# BLUESatPC104Template.net
KiCad netlist of a schematic drawn in Altium Designer
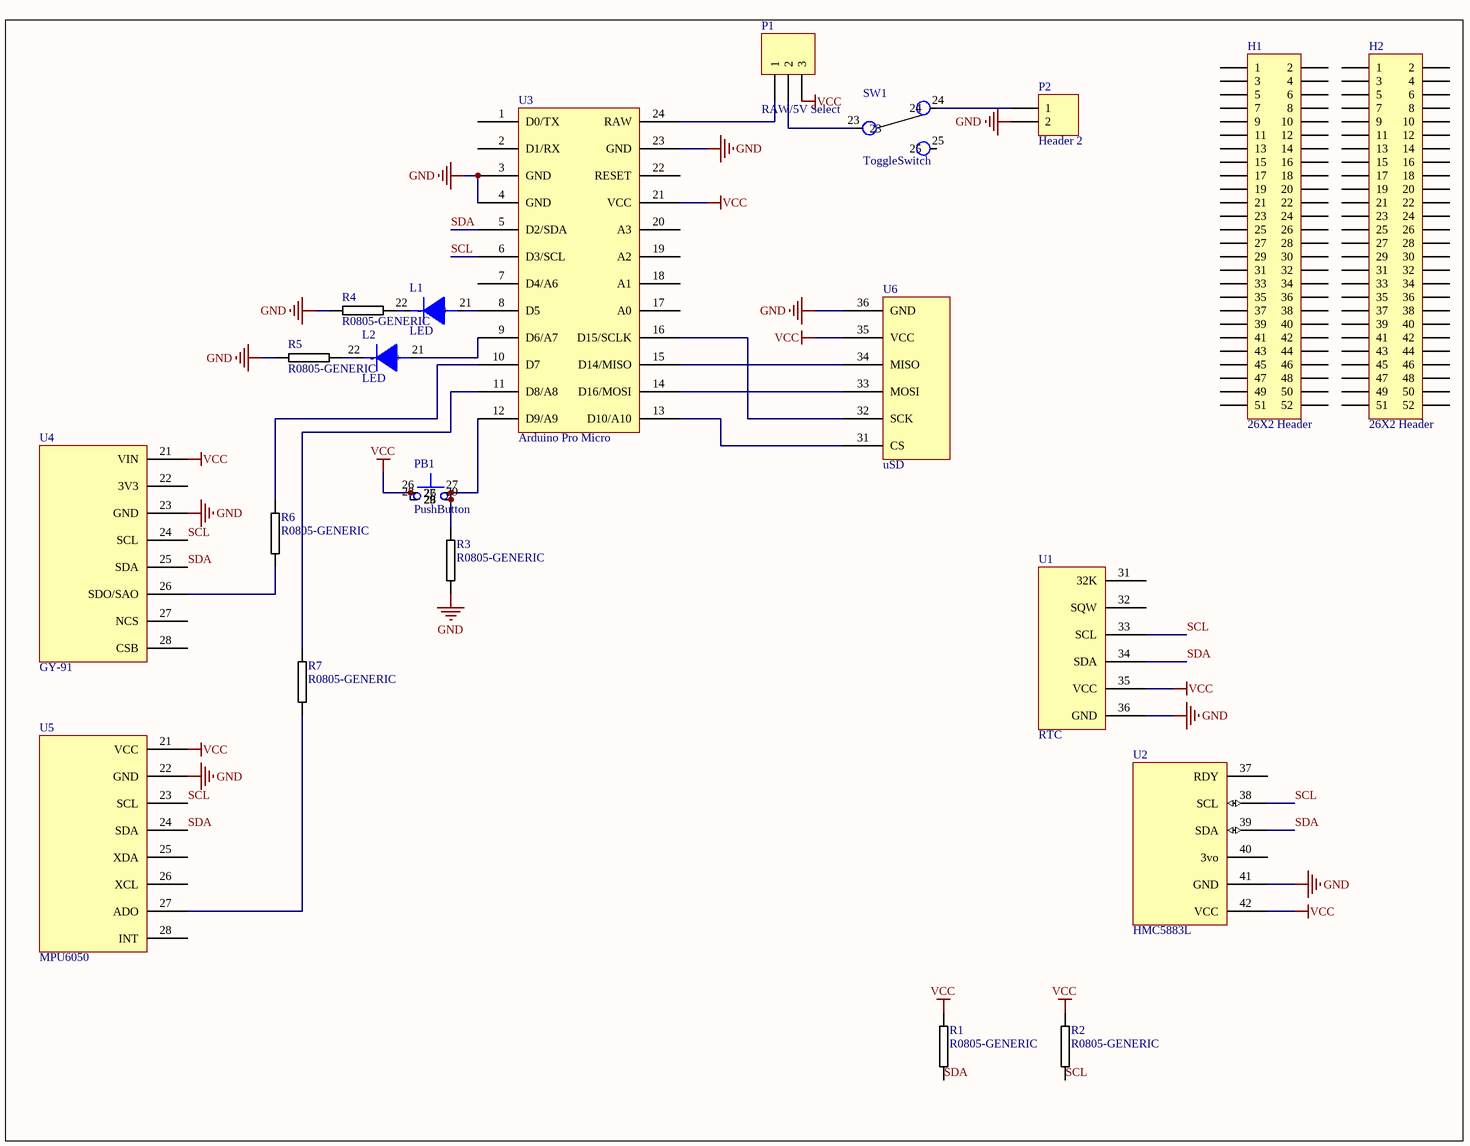
[diagram p0: BLUESatPC104Template.SchDoc]

(export (version "E")
  (design (tool "Eeschema 10.0.6"))
  (components
    (comp (ref "H1")
      (value "26X2 Header")
      (footprint "26X2 Header")
      (libsource (lib "CustomParts") (part "26X2 Header"))
    )
    (comp (ref "H2")
      (value "26X2 Header")
      (footprint "26X2 Header")
      (libsource (lib "CustomParts") (part "26X2 Header"))
    )
    (comp (ref "L1") (value "LED") (footprint "LEDFOOTPRINT") (libsource (lib "Schlib1") (part "LED")))
    (comp (ref "L2") (value "LED") (footprint "LEDFOOTPRINT") (libsource (lib "Schlib1") (part "LED")))
    (comp (ref "P1")
      (value "RAW/5V Select")
      (footprint "HDR1X3")
      (description "Header, 3-Pin")
      (fields (field (name "PUBLISHER") "Altium Limited"))
      (libsource (lib "Miscellaneous Connectors") (part "Header 3"))
    )
    (comp (ref "P2")
      (value "Header 2")
      (footprint "HDR1X2")
      (description "Header, 2-Pin")
      (fields (field (name "PUBLISHER") "Altium Limited"))
      (libsource (lib "Miscellaneous Connectors") (part "Header 2"))
    )
    (comp (ref "PB1")
      (value "PushButton")
      (footprint "PCBComponent_1")
      (libsource (lib "Schlib1") (part "PushButton"))
    )
    (comp (ref "R1")
      (value "R0805-GENERIC")
      (footprint "0805R-GENERIC")
      (description "GENERIC RESISTOR 0805")
      (libsource (lib "vh_altium_library") (part "R0805-GENERIC"))
    )
    (comp (ref "R2")
      (value "R0805-GENERIC")
      (footprint "0805R-GENERIC")
      (description "GENERIC RESISTOR 0805")
      (libsource (lib "vh_altium_library") (part "R0805-GENERIC"))
    )
    (comp (ref "R3")
      (value "R0805-GENERIC")
      (footprint "0805R-GENERIC")
      (description "GENERIC RESISTOR 0805")
      (libsource (lib "vh_altium_library") (part "R0805-GENERIC"))
    )
    (comp (ref "R4")
      (value "R0805-GENERIC")
      (footprint "0805R-GENERIC")
      (description "GENERIC RESISTOR 0805")
      (libsource (lib "vh_altium_library") (part "R0805-GENERIC"))
    )
    (comp (ref "R5")
      (value "R0805-GENERIC")
      (footprint "0805R-GENERIC")
      (description "GENERIC RESISTOR 0805")
      (libsource (lib "vh_altium_library") (part "R0805-GENERIC"))
    )
    (comp (ref "R6")
      (value "R0805-GENERIC")
      (footprint "0805R-GENERIC")
      (description "GENERIC RESISTOR 0805")
      (libsource (lib "vh_altium_library") (part "R0805-GENERIC"))
    )
    (comp (ref "R7")
      (value "R0805-GENERIC")
      (footprint "0805R-GENERIC")
      (description "GENERIC RESISTOR 0805")
      (libsource (lib "vh_altium_library") (part "R0805-GENERIC"))
    )
    (comp (ref "SW1")
      (value "ToggleSwitch")
      (footprint "SWITCHFOOTPRINT")
      (libsource (lib "Schlib1") (part "ToggleSwitch"))
    )
    (comp (ref "U1") (value "RTC") (footprint "DS3FOOTPRINT") (libsource (lib "Schlib1") (part "RTC")))
    (comp (ref "U2")
      (value "HMC5883L")
      (footprint "HMCFootprint")
      (libsource (lib "Schlib1") (part "HMC5883L"))
    )
    (comp (ref "U3")
      (value "Arduino Pro Micro")
      (footprint "Arduino Pro Micro (DIP 24)")
      (libsource (lib "POWER_BATTERY") (part "Arduino Pro Micro"))
    )
    (comp (ref "U4") (value "GY-91") (footprint "GYFOOTPRINT") (libsource (lib "Schlib1") (part "GY-91")))
    (comp (ref "U5")
      (value "MPU6050")
      (footprint "MPU6FOOTPRINT")
      (libsource (lib "Schlib1") (part "MPU6050"))
    )
    (comp (ref "U6") (value "uSD") (footprint "USDFOOTPRINT") (libsource (lib "Schlib1") (part "uSD")))
  )
  (nets
    (net (code "1") (name "/SCL") (class "Default")
      (node (ref "R2") (pin "2") (pintype "passive"))
      (node (ref "U1") (pin "33") (pinfunction "SCL_33") (pintype "passive"))
      (node (ref "U2") (pin "38") (pinfunction "SCL_38") (pintype "bidirectional"))
      (node (ref "U3") (pin "6") (pinfunction "D3/SCL_6") (pintype "passive"))
      (node (ref "U4") (pin "24") (pinfunction "SCL_24") (pintype "passive"))
      (node (ref "U5") (pin "23") (pinfunction "SCL_23") (pintype "passive"))
    )
    (net (code "2") (name "/SDA") (class "Default")
      (node (ref "R1") (pin "2") (pintype "passive"))
      (node (ref "U1") (pin "34") (pinfunction "SDA_34") (pintype "passive"))
      (node (ref "U2") (pin "39") (pinfunction "SDA_39") (pintype "bidirectional"))
      (node (ref "U3") (pin "5") (pinfunction "D2/SDA_5") (pintype "passive"))
      (node (ref "U4") (pin "25") (pinfunction "SDA_25") (pintype "passive"))
      (node (ref "U5") (pin "24") (pinfunction "SDA_24") (pintype "passive"))
    )
    (net (code "3") (name "GND") (class "Default")
      (node (ref "P2") (pin "2") (pinfunction "2_2") (pintype "passive"))
      (node (ref "R3") (pin "2") (pintype "passive"))
      (node (ref "R4") (pin "2") (pintype "passive"))
      (node (ref "R5") (pin "2") (pintype "passive"))
      (node (ref "U1") (pin "36") (pinfunction "GND_36") (pintype "passive"))
      (node (ref "U2") (pin "41") (pinfunction "GND_41") (pintype "passive"))
      (node (ref "U3") (pin "23") (pinfunction "GND_23") (pintype "passive"))
      (node (ref "U3") (pin "3") (pinfunction "GND_3") (pintype "passive"))
      (node (ref "U3") (pin "4") (pinfunction "GND_4") (pintype "passive"))
      (node (ref "U4") (pin "23") (pinfunction "GND_23") (pintype "passive"))
      (node (ref "U5") (pin "22") (pinfunction "GND_22") (pintype "passive"))
      (node (ref "U6") (pin "36") (pinfunction "GND_36") (pintype "passive"))
    )
    (net (code "4") (name "Net-(L1-+)") (class "Default")
      (node (ref "L1") (pin "21") (pinfunction "+_21") (pintype "passive"))
      (node (ref "U3") (pin "8") (pinfunction "D5_8") (pintype "passive"))
    )
    (net (code "5") (name "Net-(L1--)") (class "Default")
      (node (ref "L1") (pin "22") (pinfunction "-_22") (pintype "passive"))
      (node (ref "R4") (pin "1") (pintype "passive"))
    )
    (net (code "6") (name "Net-(L2-+)") (class "Default")
      (node (ref "L2") (pin "21") (pinfunction "+_21") (pintype "passive"))
      (node (ref "U3") (pin "9") (pinfunction "D6/A7_9") (pintype "passive"))
    )
    (net (code "7") (name "Net-(L2--)") (class "Default")
      (node (ref "L2") (pin "22") (pinfunction "-_22") (pintype "passive"))
      (node (ref "R5") (pin "1") (pintype "passive"))
    )
    (net (code "8") (name "Net-(P1-Pad2)") (class "Default")
      (node (ref "P1") (pin "2") (pinfunction "2_2") (pintype "passive"))
      (node (ref "SW1") (pin "23") (pinfunction "23_23") (pintype "passive"))
    )
    (net (code "9") (name "Net-(P2-Pad1)") (class "Default")
      (node (ref "P2") (pin "1") (pinfunction "1_1") (pintype "passive"))
      (node (ref "SW1") (pin "24") (pinfunction "24_24") (pintype "passive"))
    )
    (net (code "10") (name "Net-(U3-D7)") (class "Default")
      (node (ref "R6") (pin "1") (pintype "passive"))
      (node (ref "U3") (pin "10") (pinfunction "D7_10") (pintype "passive"))
    )
    (net (code "11") (name "Net-(U3-D8{slash}A8)") (class "Default")
      (node (ref "R7") (pin "1") (pintype "passive"))
      (node (ref "U3") (pin "11") (pinfunction "D8/A8_11") (pintype "passive"))
    )
    (net (code "12") (name "Net-(U3-D9{slash}A9)") (class "Default")
      (node (ref "PB1") (pin "27") (pinfunction "27_27") (pintype "passive"))
      (node (ref "PB1") (pin "29") (pinfunction "29_29") (pintype "passive"))
      (node (ref "R3") (pin "1") (pintype "passive"))
      (node (ref "U3") (pin "12") (pinfunction "D9/A9_12") (pintype "passive"))
    )
    (net (code "13") (name "Net-(U3-D10{slash}A10)") (class "Default")
      (node (ref "U3") (pin "13") (pinfunction "D10/A10_13") (pintype "passive"))
      (node (ref "U6") (pin "31") (pinfunction "CS_31") (pintype "passive"))
    )
    (net (code "14") (name "Net-(U3-D14{slash}MISO)") (class "Default")
      (node (ref "U3") (pin "15") (pinfunction "D14/MISO_15") (pintype "passive"))
      (node (ref "U6") (pin "34") (pinfunction "MISO_34") (pintype "passive"))
    )
    (net (code "15") (name "Net-(U3-D15{slash}SCLK)") (class "Default")
      (node (ref "U3") (pin "16") (pinfunction "D15/SCLK_16") (pintype "passive"))
      (node (ref "U6") (pin "32") (pinfunction "SCK_32") (pintype "passive"))
    )
    (net (code "16") (name "Net-(U3-D16{slash}MOSI)") (class "Default")
      (node (ref "U3") (pin "14") (pinfunction "D16/MOSI_14") (pintype "passive"))
      (node (ref "U6") (pin "33") (pinfunction "MOSI_33") (pintype "passive"))
    )
    (net (code "17") (name "Net-(U3-RAW)") (class "Default")
      (node (ref "P1") (pin "1") (pinfunction "1_1") (pintype "passive"))
      (node (ref "U3") (pin "24") (pinfunction "RAW_24") (pintype "passive"))
    )
    (net (code "18") (name "Net-(U4-SDO{slash}SAO)") (class "Default")
      (node (ref "R6") (pin "2") (pintype "passive"))
      (node (ref "U4") (pin "26") (pinfunction "SDO/SAO_26") (pintype "passive"))
    )
    (net (code "19") (name "Net-(U5-ADO)") (class "Default")
      (node (ref "R7") (pin "2") (pintype "passive"))
      (node (ref "U5") (pin "27") (pinfunction "ADO_27") (pintype "passive"))
    )
    (net (code "20") (name "VCC") (class "Default")
      (node (ref "P1") (pin "3") (pinfunction "3_3") (pintype "passive"))
      (node (ref "PB1") (pin "26") (pinfunction "26_26") (pintype "passive"))
      (node (ref "PB1") (pin "28") (pinfunction "28_28") (pintype "passive"))
      (node (ref "R1") (pin "1") (pintype "passive"))
      (node (ref "R2") (pin "1") (pintype "passive"))
      (node (ref "U1") (pin "35") (pinfunction "VCC_35") (pintype "passive"))
      (node (ref "U2") (pin "42") (pinfunction "VCC_42") (pintype "passive"))
      (node (ref "U3") (pin "21") (pinfunction "VCC_21") (pintype "passive"))
      (node (ref "U4") (pin "21") (pinfunction "VIN_21") (pintype "passive"))
      (node (ref "U5") (pin "21") (pinfunction "VCC_21") (pintype "passive"))
      (node (ref "U6") (pin "35") (pinfunction "VCC_35") (pintype "passive"))
    )
    (net (code "21") (name "unconnected-(H1-Pad1)") (class "Default")
      (node (ref "H1") (pin "1") (pinfunction "1_1") (pintype "passive"))
    )
    (net (code "22") (name "unconnected-(H1-Pad2)") (class "Default")
      (node (ref "H1") (pin "2") (pinfunction "2_2") (pintype "passive"))
    )
    (net (code "23") (name "unconnected-(H1-Pad3)") (class "Default")
      (node (ref "H1") (pin "3") (pinfunction "3_3") (pintype "passive"))
    )
    (net (code "24") (name "unconnected-(H1-Pad4)") (class "Default")
      (node (ref "H1") (pin "4") (pinfunction "4_4") (pintype "passive"))
    )
    (net (code "25") (name "unconnected-(H1-Pad5)") (class "Default")
      (node (ref "H1") (pin "5") (pinfunction "5_5") (pintype "passive"))
    )
    (net (code "26") (name "unconnected-(H1-Pad6)") (class "Default")
      (node (ref "H1") (pin "6") (pinfunction "6_6") (pintype "passive"))
    )
    (net (code "27") (name "unconnected-(H1-Pad7)") (class "Default")
      (node (ref "H1") (pin "7") (pinfunction "7_7") (pintype "passive"))
    )
    (net (code "28") (name "unconnected-(H1-Pad8)") (class "Default")
      (node (ref "H1") (pin "8") (pinfunction "8_8") (pintype "passive"))
    )
    (net (code "29") (name "unconnected-(H1-Pad9)") (class "Default")
      (node (ref "H1") (pin "9") (pinfunction "9_9") (pintype "passive"))
    )
    (net (code "30") (name "unconnected-(H1-Pad10)") (class "Default")
      (node (ref "H1") (pin "10") (pinfunction "10_10") (pintype "passive"))
    )
    (net (code "31") (name "unconnected-(H1-Pad11)") (class "Default")
      (node (ref "H1") (pin "11") (pinfunction "11_11") (pintype "passive"))
    )
    (net (code "32") (name "unconnected-(H1-Pad12)") (class "Default")
      (node (ref "H1") (pin "12") (pinfunction "12_12") (pintype "passive"))
    )
    (net (code "33") (name "unconnected-(H1-Pad13)") (class "Default")
      (node (ref "H1") (pin "13") (pinfunction "13_13") (pintype "passive"))
    )
    (net (code "34") (name "unconnected-(H1-Pad14)") (class "Default")
      (node (ref "H1") (pin "14") (pinfunction "14_14") (pintype "passive"))
    )
    (net (code "35") (name "unconnected-(H1-Pad15)") (class "Default")
      (node (ref "H1") (pin "15") (pinfunction "15_15") (pintype "passive"))
    )
    (net (code "36") (name "unconnected-(H1-Pad16)") (class "Default")
      (node (ref "H1") (pin "16") (pinfunction "16_16") (pintype "passive"))
    )
    (net (code "37") (name "unconnected-(H1-Pad17)") (class "Default")
      (node (ref "H1") (pin "17") (pinfunction "17_17") (pintype "passive"))
    )
    (net (code "38") (name "unconnected-(H1-Pad18)") (class "Default")
      (node (ref "H1") (pin "18") (pinfunction "18_18") (pintype "passive"))
    )
    (net (code "39") (name "unconnected-(H1-Pad19)") (class "Default")
      (node (ref "H1") (pin "19") (pinfunction "19_19") (pintype "passive"))
    )
    (net (code "40") (name "unconnected-(H1-Pad20)") (class "Default")
      (node (ref "H1") (pin "20") (pinfunction "20_20") (pintype "passive"))
    )
    (net (code "41") (name "unconnected-(H1-Pad21)") (class "Default")
      (node (ref "H1") (pin "21") (pinfunction "21_21") (pintype "passive"))
    )
    (net (code "42") (name "unconnected-(H1-Pad22)") (class "Default")
      (node (ref "H1") (pin "22") (pinfunction "22_22") (pintype "passive"))
    )
    (net (code "43") (name "unconnected-(H1-Pad23)") (class "Default")
      (node (ref "H1") (pin "23") (pinfunction "23_23") (pintype "passive"))
    )
    (net (code "44") (name "unconnected-(H1-Pad24)") (class "Default")
      (node (ref "H1") (pin "24") (pinfunction "24_24") (pintype "passive"))
    )
    (net (code "45") (name "unconnected-(H1-Pad25)") (class "Default")
      (node (ref "H1") (pin "25") (pinfunction "25_25") (pintype "passive"))
    )
    (net (code "46") (name "unconnected-(H1-Pad26)") (class "Default")
      (node (ref "H1") (pin "26") (pinfunction "26_26") (pintype "passive"))
    )
    (net (code "47") (name "unconnected-(H1-Pad27)") (class "Default")
      (node (ref "H1") (pin "27") (pinfunction "27_27") (pintype "passive"))
    )
    (net (code "48") (name "unconnected-(H1-Pad28)") (class "Default")
      (node (ref "H1") (pin "28") (pinfunction "28_28") (pintype "passive"))
    )
    (net (code "49") (name "unconnected-(H1-Pad29)") (class "Default")
      (node (ref "H1") (pin "29") (pinfunction "29_29") (pintype "passive"))
    )
    (net (code "50") (name "unconnected-(H1-Pad30)") (class "Default")
      (node (ref "H1") (pin "30") (pinfunction "30_30") (pintype "passive"))
    )
    (net (code "51") (name "unconnected-(H1-Pad31)") (class "Default")
      (node (ref "H1") (pin "31") (pinfunction "31_31") (pintype "passive"))
    )
    (net (code "52") (name "unconnected-(H1-Pad32)") (class "Default")
      (node (ref "H1") (pin "32") (pinfunction "32_32") (pintype "passive"))
    )
    (net (code "53") (name "unconnected-(H1-Pad33)") (class "Default")
      (node (ref "H1") (pin "33") (pinfunction "33_33") (pintype "passive"))
    )
    (net (code "54") (name "unconnected-(H1-Pad34)") (class "Default")
      (node (ref "H1") (pin "34") (pinfunction "34_34") (pintype "passive"))
    )
    (net (code "55") (name "unconnected-(H1-Pad35)") (class "Default")
      (node (ref "H1") (pin "35") (pinfunction "35_35") (pintype "passive"))
    )
    (net (code "56") (name "unconnected-(H1-Pad36)") (class "Default")
      (node (ref "H1") (pin "36") (pinfunction "36_36") (pintype "passive"))
    )
    (net (code "57") (name "unconnected-(H1-Pad37)") (class "Default")
      (node (ref "H1") (pin "37") (pinfunction "37_37") (pintype "passive"))
    )
    (net (code "58") (name "unconnected-(H1-Pad38)") (class "Default")
      (node (ref "H1") (pin "38") (pinfunction "38_38") (pintype "passive"))
    )
    (net (code "59") (name "unconnected-(H1-Pad39)") (class "Default")
      (node (ref "H1") (pin "39") (pinfunction "39_39") (pintype "passive"))
    )
    (net (code "60") (name "unconnected-(H1-Pad40)") (class "Default")
      (node (ref "H1") (pin "40") (pinfunction "40_40") (pintype "passive"))
    )
    (net (code "61") (name "unconnected-(H1-Pad41)") (class "Default")
      (node (ref "H1") (pin "41") (pinfunction "41_41") (pintype "passive"))
    )
    (net (code "62") (name "unconnected-(H1-Pad42)") (class "Default")
      (node (ref "H1") (pin "42") (pinfunction "42_42") (pintype "passive"))
    )
    (net (code "63") (name "unconnected-(H1-Pad43)") (class "Default")
      (node (ref "H1") (pin "43") (pinfunction "43_43") (pintype "passive"))
    )
    (net (code "64") (name "unconnected-(H1-Pad44)") (class "Default")
      (node (ref "H1") (pin "44") (pinfunction "44_44") (pintype "passive"))
    )
    (net (code "65") (name "unconnected-(H1-Pad45)") (class "Default")
      (node (ref "H1") (pin "45") (pinfunction "45_45") (pintype "passive"))
    )
    (net (code "66") (name "unconnected-(H1-Pad46)") (class "Default")
      (node (ref "H1") (pin "46") (pinfunction "46_46") (pintype "passive"))
    )
    (net (code "67") (name "unconnected-(H1-Pad47)") (class "Default")
      (node (ref "H1") (pin "47") (pinfunction "47_47") (pintype "passive"))
    )
    (net (code "68") (name "unconnected-(H1-Pad48)") (class "Default")
      (node (ref "H1") (pin "48") (pinfunction "48_48") (pintype "passive"))
    )
    (net (code "69") (name "unconnected-(H1-Pad49)") (class "Default")
      (node (ref "H1") (pin "49") (pinfunction "49_49") (pintype "passive"))
    )
    (net (code "70") (name "unconnected-(H1-Pad50)") (class "Default")
      (node (ref "H1") (pin "50") (pinfunction "50_50") (pintype "passive"))
    )
    (net (code "71") (name "unconnected-(H1-Pad51)") (class "Default")
      (node (ref "H1") (pin "51") (pinfunction "51_51") (pintype "passive"))
    )
    (net (code "72") (name "unconnected-(H1-Pad52)") (class "Default")
      (node (ref "H1") (pin "52") (pinfunction "52_52") (pintype "passive"))
    )
    (net (code "73") (name "unconnected-(H2-Pad1)") (class "Default")
      (node (ref "H2") (pin "1") (pinfunction "1_1") (pintype "passive"))
    )
    (net (code "74") (name "unconnected-(H2-Pad2)") (class "Default")
      (node (ref "H2") (pin "2") (pinfunction "2_2") (pintype "passive"))
    )
    (net (code "75") (name "unconnected-(H2-Pad3)") (class "Default")
      (node (ref "H2") (pin "3") (pinfunction "3_3") (pintype "passive"))
    )
    (net (code "76") (name "unconnected-(H2-Pad4)") (class "Default")
      (node (ref "H2") (pin "4") (pinfunction "4_4") (pintype "passive"))
    )
    (net (code "77") (name "unconnected-(H2-Pad5)") (class "Default")
      (node (ref "H2") (pin "5") (pinfunction "5_5") (pintype "passive"))
    )
    (net (code "78") (name "unconnected-(H2-Pad6)") (class "Default")
      (node (ref "H2") (pin "6") (pinfunction "6_6") (pintype "passive"))
    )
    (net (code "79") (name "unconnected-(H2-Pad7)") (class "Default")
      (node (ref "H2") (pin "7") (pinfunction "7_7") (pintype "passive"))
    )
    (net (code "80") (name "unconnected-(H2-Pad8)") (class "Default")
      (node (ref "H2") (pin "8") (pinfunction "8_8") (pintype "passive"))
    )
    (net (code "81") (name "unconnected-(H2-Pad9)") (class "Default")
      (node (ref "H2") (pin "9") (pinfunction "9_9") (pintype "passive"))
    )
    (net (code "82") (name "unconnected-(H2-Pad10)") (class "Default")
      (node (ref "H2") (pin "10") (pinfunction "10_10") (pintype "passive"))
    )
    (net (code "83") (name "unconnected-(H2-Pad11)") (class "Default")
      (node (ref "H2") (pin "11") (pinfunction "11_11") (pintype "passive"))
    )
    (net (code "84") (name "unconnected-(H2-Pad12)") (class "Default")
      (node (ref "H2") (pin "12") (pinfunction "12_12") (pintype "passive"))
    )
    (net (code "85") (name "unconnected-(H2-Pad13)") (class "Default")
      (node (ref "H2") (pin "13") (pinfunction "13_13") (pintype "passive"))
    )
    (net (code "86") (name "unconnected-(H2-Pad14)") (class "Default")
      (node (ref "H2") (pin "14") (pinfunction "14_14") (pintype "passive"))
    )
    (net (code "87") (name "unconnected-(H2-Pad15)") (class "Default")
      (node (ref "H2") (pin "15") (pinfunction "15_15") (pintype "passive"))
    )
    (net (code "88") (name "unconnected-(H2-Pad16)") (class "Default")
      (node (ref "H2") (pin "16") (pinfunction "16_16") (pintype "passive"))
    )
    (net (code "89") (name "unconnected-(H2-Pad17)") (class "Default")
      (node (ref "H2") (pin "17") (pinfunction "17_17") (pintype "passive"))
    )
    (net (code "90") (name "unconnected-(H2-Pad18)") (class "Default")
      (node (ref "H2") (pin "18") (pinfunction "18_18") (pintype "passive"))
    )
    (net (code "91") (name "unconnected-(H2-Pad19)") (class "Default")
      (node (ref "H2") (pin "19") (pinfunction "19_19") (pintype "passive"))
    )
    (net (code "92") (name "unconnected-(H2-Pad20)") (class "Default")
      (node (ref "H2") (pin "20") (pinfunction "20_20") (pintype "passive"))
    )
    (net (code "93") (name "unconnected-(H2-Pad21)") (class "Default")
      (node (ref "H2") (pin "21") (pinfunction "21_21") (pintype "passive"))
    )
    (net (code "94") (name "unconnected-(H2-Pad22)") (class "Default")
      (node (ref "H2") (pin "22") (pinfunction "22_22") (pintype "passive"))
    )
    (net (code "95") (name "unconnected-(H2-Pad23)") (class "Default")
      (node (ref "H2") (pin "23") (pinfunction "23_23") (pintype "passive"))
    )
    (net (code "96") (name "unconnected-(H2-Pad24)") (class "Default")
      (node (ref "H2") (pin "24") (pinfunction "24_24") (pintype "passive"))
    )
    (net (code "97") (name "unconnected-(H2-Pad25)") (class "Default")
      (node (ref "H2") (pin "25") (pinfunction "25_25") (pintype "passive"))
    )
    (net (code "98") (name "unconnected-(H2-Pad26)") (class "Default")
      (node (ref "H2") (pin "26") (pinfunction "26_26") (pintype "passive"))
    )
    (net (code "99") (name "unconnected-(H2-Pad27)") (class "Default")
      (node (ref "H2") (pin "27") (pinfunction "27_27") (pintype "passive"))
    )
    (net (code "100") (name "unconnected-(H2-Pad28)") (class "Default")
      (node (ref "H2") (pin "28") (pinfunction "28_28") (pintype "passive"))
    )
    (net (code "101") (name "unconnected-(H2-Pad29)") (class "Default")
      (node (ref "H2") (pin "29") (pinfunction "29_29") (pintype "passive"))
    )
    (net (code "102") (name "unconnected-(H2-Pad30)") (class "Default")
      (node (ref "H2") (pin "30") (pinfunction "30_30") (pintype "passive"))
    )
    (net (code "103") (name "unconnected-(H2-Pad31)") (class "Default")
      (node (ref "H2") (pin "31") (pinfunction "31_31") (pintype "passive"))
    )
    (net (code "104") (name "unconnected-(H2-Pad32)") (class "Default")
      (node (ref "H2") (pin "32") (pinfunction "32_32") (pintype "passive"))
    )
    (net (code "105") (name "unconnected-(H2-Pad33)") (class "Default")
      (node (ref "H2") (pin "33") (pinfunction "33_33") (pintype "passive"))
    )
    (net (code "106") (name "unconnected-(H2-Pad34)") (class "Default")
      (node (ref "H2") (pin "34") (pinfunction "34_34") (pintype "passive"))
    )
    (net (code "107") (name "unconnected-(H2-Pad35)") (class "Default")
      (node (ref "H2") (pin "35") (pinfunction "35_35") (pintype "passive"))
    )
    (net (code "108") (name "unconnected-(H2-Pad36)") (class "Default")
      (node (ref "H2") (pin "36") (pinfunction "36_36") (pintype "passive"))
    )
    (net (code "109") (name "unconnected-(H2-Pad37)") (class "Default")
      (node (ref "H2") (pin "37") (pinfunction "37_37") (pintype "passive"))
    )
    (net (code "110") (name "unconnected-(H2-Pad38)") (class "Default")
      (node (ref "H2") (pin "38") (pinfunction "38_38") (pintype "passive"))
    )
    (net (code "111") (name "unconnected-(H2-Pad39)") (class "Default")
      (node (ref "H2") (pin "39") (pinfunction "39_39") (pintype "passive"))
    )
    (net (code "112") (name "unconnected-(H2-Pad40)") (class "Default")
      (node (ref "H2") (pin "40") (pinfunction "40_40") (pintype "passive"))
    )
    (net (code "113") (name "unconnected-(H2-Pad41)") (class "Default")
      (node (ref "H2") (pin "41") (pinfunction "41_41") (pintype "passive"))
    )
    (net (code "114") (name "unconnected-(H2-Pad42)") (class "Default")
      (node (ref "H2") (pin "42") (pinfunction "42_42") (pintype "passive"))
    )
    (net (code "115") (name "unconnected-(H2-Pad43)") (class "Default")
      (node (ref "H2") (pin "43") (pinfunction "43_43") (pintype "passive"))
    )
    (net (code "116") (name "unconnected-(H2-Pad44)") (class "Default")
      (node (ref "H2") (pin "44") (pinfunction "44_44") (pintype "passive"))
    )
    (net (code "117") (name "unconnected-(H2-Pad45)") (class "Default")
      (node (ref "H2") (pin "45") (pinfunction "45_45") (pintype "passive"))
    )
    (net (code "118") (name "unconnected-(H2-Pad46)") (class "Default")
      (node (ref "H2") (pin "46") (pinfunction "46_46") (pintype "passive"))
    )
    (net (code "119") (name "unconnected-(H2-Pad47)") (class "Default")
      (node (ref "H2") (pin "47") (pinfunction "47_47") (pintype "passive"))
    )
    (net (code "120") (name "unconnected-(H2-Pad48)") (class "Default")
      (node (ref "H2") (pin "48") (pinfunction "48_48") (pintype "passive"))
    )
    (net (code "121") (name "unconnected-(H2-Pad49)") (class "Default")
      (node (ref "H2") (pin "49") (pinfunction "49_49") (pintype "passive"))
    )
    (net (code "122") (name "unconnected-(H2-Pad50)") (class "Default")
      (node (ref "H2") (pin "50") (pinfunction "50_50") (pintype "passive"))
    )
    (net (code "123") (name "unconnected-(H2-Pad51)") (class "Default")
      (node (ref "H2") (pin "51") (pinfunction "51_51") (pintype "passive"))
    )
    (net (code "124") (name "unconnected-(H2-Pad52)") (class "Default")
      (node (ref "H2") (pin "52") (pinfunction "52_52") (pintype "passive"))
    )
    (net (code "125") (name "unconnected-(SW1-Pad25)") (class "Default")
      (node (ref "SW1") (pin "25") (pinfunction "25_25") (pintype "passive"))
    )
    (net (code "126") (name "unconnected-(U1-32K-Pad31)") (class "Default")
      (node (ref "U1") (pin "31") (pinfunction "32K_31") (pintype "passive"))
    )
    (net (code "127") (name "unconnected-(U1-SQW-Pad32)") (class "Default")
      (node (ref "U1") (pin "32") (pinfunction "SQW_32") (pintype "passive"))
    )
    (net (code "128") (name "unconnected-(U2-3vo-Pad40)") (class "Default")
      (node (ref "U2") (pin "40") (pinfunction "3vo_40") (pintype "passive"))
    )
    (net (code "129") (name "unconnected-(U2-RDY-Pad37)") (class "Default")
      (node (ref "U2") (pin "37") (pinfunction "RDY_37") (pintype "passive"))
    )
    (net (code "130") (name "unconnected-(U3-A0-Pad17)") (class "Default")
      (node (ref "U3") (pin "17") (pinfunction "A0_17") (pintype "passive"))
    )
    (net (code "131") (name "unconnected-(U3-A1-Pad18)") (class "Default")
      (node (ref "U3") (pin "18") (pinfunction "A1_18") (pintype "passive"))
    )
    (net (code "132") (name "unconnected-(U3-A2-Pad19)") (class "Default")
      (node (ref "U3") (pin "19") (pinfunction "A2_19") (pintype "passive"))
    )
    (net (code "133") (name "unconnected-(U3-A3-Pad20)") (class "Default")
      (node (ref "U3") (pin "20") (pinfunction "A3_20") (pintype "passive"))
    )
    (net (code "134") (name "unconnected-(U3-D0{slash}TX-Pad1)") (class "Default")
      (node (ref "U3") (pin "1") (pinfunction "D0/TX_1") (pintype "passive"))
    )
    (net (code "135") (name "unconnected-(U3-D1{slash}RX-Pad2)") (class "Default")
      (node (ref "U3") (pin "2") (pinfunction "D1/RX_2") (pintype "passive"))
    )
    (net (code "136") (name "unconnected-(U3-D4{slash}A6-Pad7)") (class "Default")
      (node (ref "U3") (pin "7") (pinfunction "D4/A6_7") (pintype "passive"))
    )
    (net (code "137") (name "unconnected-(U3-RESET-Pad22)") (class "Default")
      (node (ref "U3") (pin "22") (pinfunction "RESET_22") (pintype "passive"))
    )
    (net (code "138") (name "unconnected-(U4-3V3-Pad22)") (class "Default")
      (node (ref "U4") (pin "22") (pinfunction "3V3_22") (pintype "passive"))
    )
    (net (code "139") (name "unconnected-(U4-CSB-Pad28)") (class "Default")
      (node (ref "U4") (pin "28") (pinfunction "CSB_28") (pintype "passive"))
    )
    (net (code "140") (name "unconnected-(U4-NCS-Pad27)") (class "Default")
      (node (ref "U4") (pin "27") (pinfunction "NCS_27") (pintype "passive"))
    )
    (net (code "141") (name "unconnected-(U5-INT-Pad28)") (class "Default")
      (node (ref "U5") (pin "28") (pinfunction "INT_28") (pintype "passive"))
    )
    (net (code "142") (name "unconnected-(U5-XCL-Pad26)") (class "Default")
      (node (ref "U5") (pin "26") (pinfunction "XCL_26") (pintype "passive"))
    )
    (net (code "143") (name "unconnected-(U5-XDA-Pad25)") (class "Default")
      (node (ref "U5") (pin "25") (pinfunction "XDA_25") (pintype "passive"))
    )
  )
)
